# 2te8LED_v03.net
KiCad netlist of a schematic drawn in EAGLE
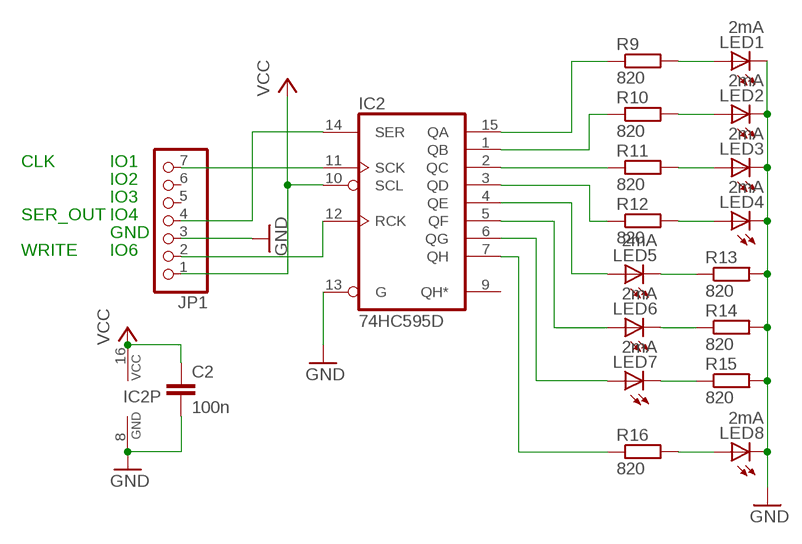
[diagram p0: schematic, sheet 1]

(export (version "E")
  (design (tool "Eeschema 10.0.6"))
  (components
    (comp (ref "C2")
      (value "100n")
      (footprint "eagle-import:C050-024X044")
      (libsource (lib "eagle-import") (part "C-EU050-024X044"))
    )
    (comp (ref "IC2")
      (value "74HC595D")
      (footprint "eagle-import:SO16")
      (libsource (lib "eagle-import") (part "74595DHC"))
    )
    (comp (ref "JP1")
      (value "PINHD-1X7_2.54")
      (footprint "eagle-import:1X07")
      (libsource (lib "eagle-import") (part "PINHD-1X7_2.54"))
    )
    (comp (ref "LED1")
      (value "2mA")
      (footprint "eagle-import:LED3MM")
      (libsource (lib "eagle-import") (part "LED3MM"))
    )
    (comp (ref "LED2")
      (value "2mA")
      (footprint "eagle-import:LED3MM")
      (libsource (lib "eagle-import") (part "LED3MM"))
    )
    (comp (ref "LED3")
      (value "2mA")
      (footprint "eagle-import:LED3MM")
      (libsource (lib "eagle-import") (part "LED3MM"))
    )
    (comp (ref "LED4")
      (value "2mA")
      (footprint "eagle-import:LED3MM")
      (libsource (lib "eagle-import") (part "LED3MM"))
    )
    (comp (ref "LED5")
      (value "2mA")
      (footprint "eagle-import:LED3MM")
      (libsource (lib "eagle-import") (part "LED3MM"))
    )
    (comp (ref "LED6")
      (value "2mA")
      (footprint "eagle-import:LED3MM")
      (libsource (lib "eagle-import") (part "LED3MM"))
    )
    (comp (ref "LED7")
      (value "2mA")
      (footprint "eagle-import:LED3MM")
      (libsource (lib "eagle-import") (part "LED3MM"))
    )
    (comp (ref "LED8")
      (value "2mA")
      (footprint "eagle-import:LED3MM")
      (libsource (lib "eagle-import") (part "LED3MM"))
    )
    (comp (ref "R9")
      (value "820")
      (footprint "eagle-import:0204_7")
      (libsource (lib "eagle-import") (part "R-EU_0204/7"))
    )
    (comp (ref "R10")
      (value "820")
      (footprint "eagle-import:0204_7")
      (libsource (lib "eagle-import") (part "R-EU_0204/7"))
    )
    (comp (ref "R11")
      (value "820")
      (footprint "eagle-import:0204_7")
      (libsource (lib "eagle-import") (part "R-EU_0204/7"))
    )
    (comp (ref "R12")
      (value "820")
      (footprint "eagle-import:0204_7")
      (libsource (lib "eagle-import") (part "R-EU_0204/7"))
    )
    (comp (ref "R13")
      (value "820")
      (footprint "eagle-import:0204_7")
      (libsource (lib "eagle-import") (part "R-EU_0204/7"))
    )
    (comp (ref "R14")
      (value "820")
      (footprint "eagle-import:0204_7")
      (libsource (lib "eagle-import") (part "R-EU_0204/7"))
    )
    (comp (ref "R15")
      (value "820")
      (footprint "eagle-import:0204_7")
      (libsource (lib "eagle-import") (part "R-EU_0204/7"))
    )
    (comp (ref "R16")
      (value "820")
      (footprint "eagle-import:0204_7")
      (libsource (lib "eagle-import") (part "R-EU_0204/7"))
    )
  )
  (nets
    (net (code "1") (name "GND") (class "Default")
      (node (ref "C2") (pin "2") (pinfunction "2_2") (pintype "passive"))
      (node (ref "IC2") (pin "13") (pinfunction "G_13") (pintype "input"))
      (node (ref "IC2") (pin "8") (pinfunction "GND_8") (pintype "power_in"))
      (node (ref "JP1") (pin "3") (pinfunction "3_3") (pintype "passive"))
      (node (ref "LED1") (pin "K") (pinfunction "C_K") (pintype "passive"))
      (node (ref "LED2") (pin "K") (pinfunction "C_K") (pintype "passive"))
      (node (ref "LED3") (pin "K") (pinfunction "C_K") (pintype "passive"))
      (node (ref "LED4") (pin "K") (pinfunction "C_K") (pintype "passive"))
      (node (ref "LED8") (pin "K") (pinfunction "C_K") (pintype "passive"))
      (node (ref "R13") (pin "2") (pinfunction "2_2") (pintype "passive"))
      (node (ref "R14") (pin "2") (pinfunction "2_2") (pintype "passive"))
      (node (ref "R15") (pin "2") (pinfunction "2_2") (pintype "passive"))
    )
    (net (code "2") (name "Net-(IC2A-QA)") (class "Default")
      (node (ref "IC2") (pin "15") (pinfunction "QA_15") (pintype "tri_state"))
      (node (ref "R9") (pin "1") (pinfunction "1_1") (pintype "passive"))
    )
    (net (code "3") (name "Net-(IC2A-QB)") (class "Default")
      (node (ref "IC2") (pin "1") (pinfunction "QB_1") (pintype "tri_state"))
      (node (ref "R10") (pin "1") (pinfunction "1_1") (pintype "passive"))
    )
    (net (code "4") (name "Net-(IC2A-QC)") (class "Default")
      (node (ref "IC2") (pin "2") (pinfunction "QC_2") (pintype "tri_state"))
      (node (ref "R11") (pin "1") (pinfunction "1_1") (pintype "passive"))
    )
    (net (code "5") (name "Net-(IC2A-QD)") (class "Default")
      (node (ref "IC2") (pin "3") (pinfunction "QD_3") (pintype "tri_state"))
      (node (ref "R12") (pin "1") (pinfunction "1_1") (pintype "passive"))
    )
    (net (code "6") (name "Net-(IC2A-QE)") (class "Default")
      (node (ref "IC2") (pin "4") (pinfunction "QE_4") (pintype "tri_state"))
      (node (ref "LED5") (pin "A") (pinfunction "A_A") (pintype "passive"))
    )
    (net (code "7") (name "Net-(IC2A-QF)") (class "Default")
      (node (ref "IC2") (pin "5") (pinfunction "QF_5") (pintype "tri_state"))
      (node (ref "LED6") (pin "A") (pinfunction "A_A") (pintype "passive"))
    )
    (net (code "8") (name "Net-(IC2A-QG)") (class "Default")
      (node (ref "IC2") (pin "6") (pinfunction "QG_6") (pintype "tri_state"))
      (node (ref "LED7") (pin "A") (pinfunction "A_A") (pintype "passive"))
    )
    (net (code "9") (name "Net-(IC2A-QH)") (class "Default")
      (node (ref "IC2") (pin "7") (pinfunction "QH_7") (pintype "tri_state"))
      (node (ref "R16") (pin "1") (pinfunction "1_1") (pintype "passive"))
    )
    (net (code "10") (name "Net-(IC2A-RCK)") (class "Default")
      (node (ref "IC2") (pin "12") (pinfunction "RCK_12") (pintype "input"))
      (node (ref "JP1") (pin "2") (pinfunction "2_2") (pintype "passive"))
    )
    (net (code "11") (name "Net-(IC2A-SCK)") (class "Default")
      (node (ref "IC2") (pin "11") (pinfunction "SCK_11") (pintype "input"))
      (node (ref "JP1") (pin "7") (pinfunction "7_7") (pintype "passive"))
    )
    (net (code "12") (name "Net-(IC2A-SER)") (class "Default")
      (node (ref "IC2") (pin "14") (pinfunction "SER_14") (pintype "input"))
      (node (ref "JP1") (pin "4") (pinfunction "4_4") (pintype "passive"))
    )
    (net (code "13") (name "Net-(LED1-PadA)") (class "Default")
      (node (ref "LED1") (pin "A") (pinfunction "A_A") (pintype "passive"))
      (node (ref "R9") (pin "2") (pinfunction "2_2") (pintype "passive"))
    )
    (net (code "14") (name "Net-(LED2-PadA)") (class "Default")
      (node (ref "LED2") (pin "A") (pinfunction "A_A") (pintype "passive"))
      (node (ref "R10") (pin "2") (pinfunction "2_2") (pintype "passive"))
    )
    (net (code "15") (name "Net-(LED3-PadA)") (class "Default")
      (node (ref "LED3") (pin "A") (pinfunction "A_A") (pintype "passive"))
      (node (ref "R11") (pin "2") (pinfunction "2_2") (pintype "passive"))
    )
    (net (code "16") (name "Net-(LED4-PadA)") (class "Default")
      (node (ref "LED4") (pin "A") (pinfunction "A_A") (pintype "passive"))
      (node (ref "R12") (pin "2") (pinfunction "2_2") (pintype "passive"))
    )
    (net (code "17") (name "Net-(LED5-C)") (class "Default")
      (node (ref "LED5") (pin "K") (pinfunction "C_K") (pintype "passive"))
      (node (ref "R13") (pin "1") (pinfunction "1_1") (pintype "passive"))
    )
    (net (code "18") (name "Net-(LED6-C)") (class "Default")
      (node (ref "LED6") (pin "K") (pinfunction "C_K") (pintype "passive"))
      (node (ref "R14") (pin "1") (pinfunction "1_1") (pintype "passive"))
    )
    (net (code "19") (name "Net-(LED7-C)") (class "Default")
      (node (ref "LED7") (pin "K") (pinfunction "C_K") (pintype "passive"))
      (node (ref "R15") (pin "1") (pinfunction "1_1") (pintype "passive"))
    )
    (net (code "20") (name "Net-(LED8-PadA)") (class "Default")
      (node (ref "LED8") (pin "A") (pinfunction "A_A") (pintype "passive"))
      (node (ref "R16") (pin "2") (pinfunction "2_2") (pintype "passive"))
    )
    (net (code "21") (name "VCC") (class "Default")
      (node (ref "C2") (pin "1") (pinfunction "1_1") (pintype "passive"))
      (node (ref "IC2") (pin "10") (pinfunction "SCL_10") (pintype "input"))
      (node (ref "IC2") (pin "16") (pinfunction "VCC_16") (pintype "power_in"))
      (node (ref "JP1") (pin "1") (pinfunction "1_1") (pintype "passive"))
    )
    (net (code "22") (name "unconnected-(IC2A-QH*-Pad9)") (class "Default")
      (node (ref "IC2") (pin "9") (pinfunction "QH*_9") (pintype "tri_state"))
    )
    (net (code "23") (name "unconnected-(JP1-Pad5)") (class "Default")
      (node (ref "JP1") (pin "5") (pinfunction "5_5") (pintype "passive"))
    )
    (net (code "24") (name "unconnected-(JP1-Pad6)") (class "Default")
      (node (ref "JP1") (pin "6") (pinfunction "6_6") (pintype "passive"))
    )
  )
)
